# MGT_1_8V.net
KiCad netlist of a schematic drawn in Altium Designer
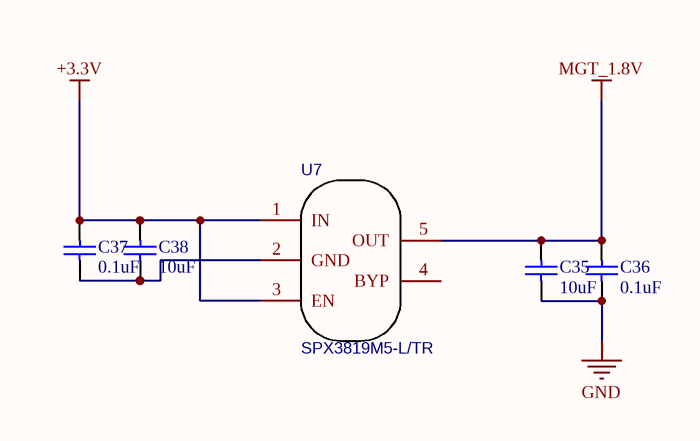
[diagram p0: MGT_1.8V.SchDoc]

(export (version "E")
  (design (tool "Eeschema 10.0.6"))
  (components
    (comp (ref "C35")
      (value "10uF")
      (footprint "C1210")
      (description "Capacitor (Semiconductor SIM Model)")
      (fields (field (name "Comment") "Cap Semi") (field (name "PUBLISHER") "Altium Limited"))
      (libsource (lib "Miscellaneous Devices") (part "Cap Semi"))
    )
    (comp (ref "C36")
      (value "0.1uF")
      (footprint "C1210")
      (description "Capacitor (Semiconductor SIM Model)")
      (fields (field (name "Comment") "Cap Semi") (field (name "PUBLISHER") "Altium Limited"))
      (libsource (lib "Miscellaneous Devices") (part "Cap Semi"))
    )
    (comp (ref "C37")
      (value "0.1uF")
      (footprint "C1210")
      (description "Capacitor (Semiconductor SIM Model)")
      (fields (field (name "Comment") "Cap Semi") (field (name "PUBLISHER") "Altium Limited"))
      (libsource (lib "Miscellaneous Devices") (part "Cap Semi"))
    )
    (comp (ref "C38")
      (value "10uF")
      (footprint "C1210")
      (description "Capacitor (Semiconductor SIM Model)")
      (fields (field (name "Comment") "Cap Semi") (field (name "PUBLISHER") "Altium Limited"))
      (libsource (lib "Miscellaneous Devices") (part "Cap Semi"))
    )
    (comp (ref "U7")
      (value "SPX3819M5-L/TR")
      (footprint "SOT-23-5_L3.0-W1.7-P0.95-LS2.8-BL")
      (fields (field (name "BOM_SUPPLIER PART") "C9056"))
      (libsource (lib "power_chip") (part "SPX3819M5-L/TR"))
    )
  )
  (nets
    (net (code "1") (name "+3.3V") (class "Default")
      (node (ref "C37") (pin "1") (pinfunction "1_1") (pintype "passive"))
      (node (ref "C38") (pin "1") (pinfunction "1_1") (pintype "passive"))
      (node (ref "U7") (pin "1") (pinfunction "IN_1") (pintype "passive"))
      (node (ref "U7") (pin "3") (pinfunction "EN_3") (pintype "passive"))
    )
    (net (code "2") (name "GND") (class "Default")
      (node (ref "C35") (pin "2") (pinfunction "2_2") (pintype "passive"))
      (node (ref "C36") (pin "2") (pinfunction "2_2") (pintype "passive"))
    )
    (net (code "3") (name "MGT_1.8V") (class "Default")
      (node (ref "C35") (pin "1") (pinfunction "1_1") (pintype "passive"))
      (node (ref "C36") (pin "1") (pinfunction "1_1") (pintype "passive"))
      (node (ref "U7") (pin "5") (pinfunction "OUT_5") (pintype "passive"))
    )
    (net (code "4") (name "Net-(U7-GND)") (class "Default")
      (node (ref "C37") (pin "2") (pinfunction "2_2") (pintype "passive"))
      (node (ref "C38") (pin "2") (pinfunction "2_2") (pintype "passive"))
      (node (ref "U7") (pin "2") (pinfunction "GND_2") (pintype "passive"))
    )
    (net (code "5") (name "unconnected-(U7-BYP-Pad4)") (class "Default")
      (node (ref "U7") (pin "4") (pinfunction "BYP_4") (pintype "passive"))
    )
  )
)
